# c150_rev_b.net
KiCad netlist of a schematic drawn in EAGLE
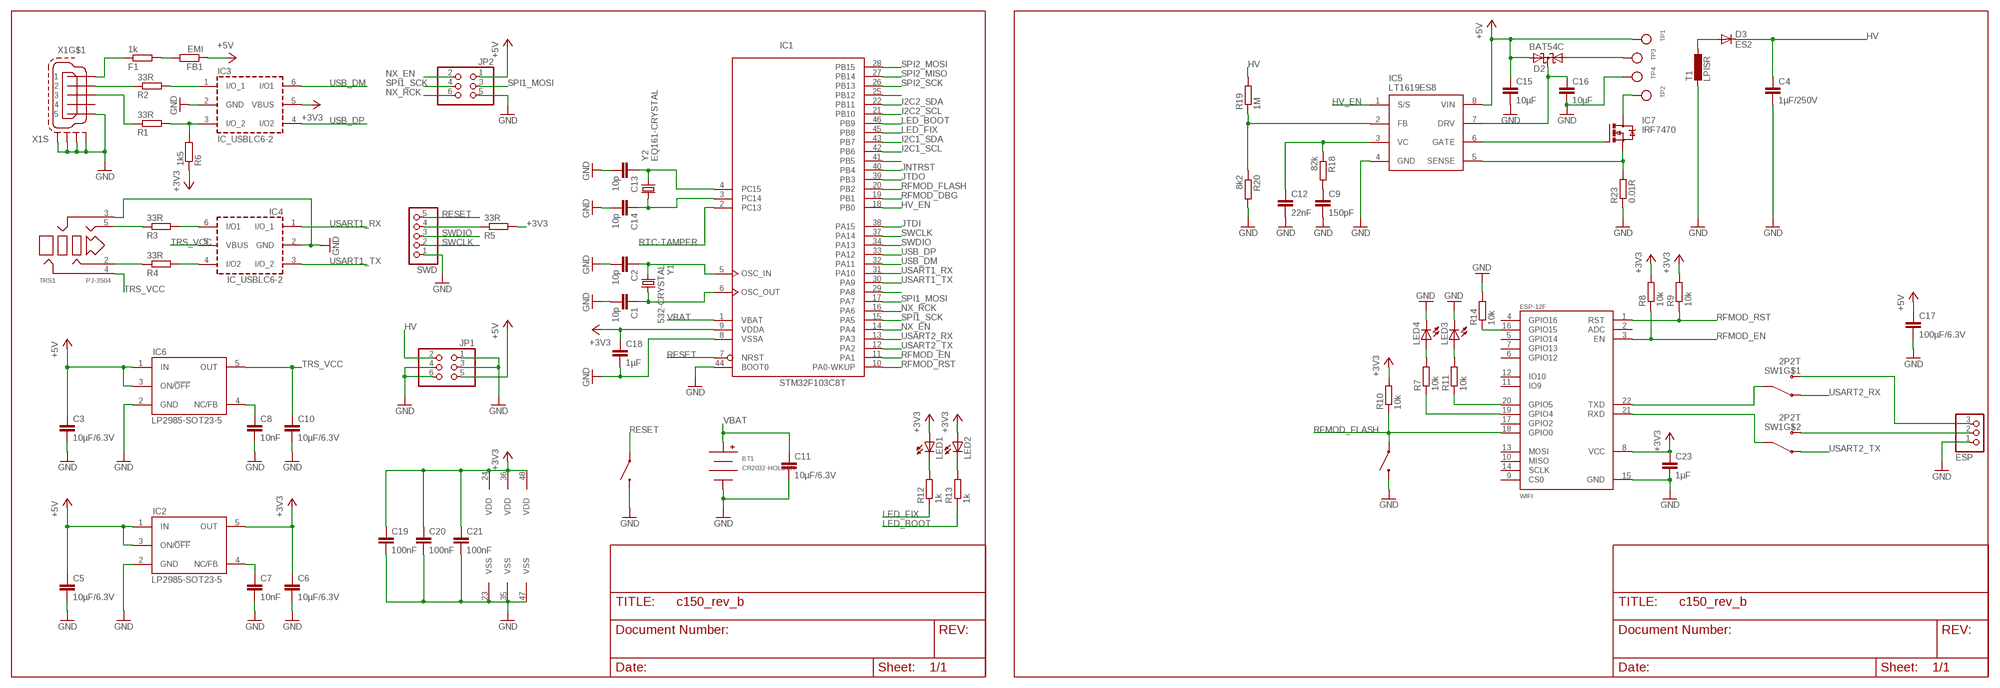
[diagram p0: schematic, sheet 1]

(export (version "E")
  (design (tool "Eeschema 10.0.6"))
  (components
    (comp (ref "BT1")
      (value "CR2032-HOLDER")
      (footprint "eagle-import:CH28-2032LF")
      (libsource (lib "eagle-import") (part "CR2032-HOLDER"))
    )
    (comp (ref "C1")
      (value "10p")
      (footprint "eagle-import:C0603")
      (libsource (lib "eagle-import") (part "C-EUC0603"))
    )
    (comp (ref "C2")
      (value "10p")
      (footprint "eagle-import:C0603")
      (libsource (lib "eagle-import") (part "C-EUC0603"))
    )
    (comp (ref "C3")
      (value "10µF/6.3V")
      (footprint "eagle-import:C0603")
      (libsource (lib "eagle-import") (part "C-EUC0603"))
    )
    (comp (ref "C4")
      (value "1µF/250V")
      (footprint "eagle-import:C2220K")
      (libsource (lib "eagle-import") (part "C-EUC2220K"))
    )
    (comp (ref "C5")
      (value "10µF/6.3V")
      (footprint "eagle-import:C0603")
      (libsource (lib "eagle-import") (part "C-EUC0603"))
    )
    (comp (ref "C6")
      (value "10µF/6.3V")
      (footprint "eagle-import:C0603")
      (libsource (lib "eagle-import") (part "C-EUC0603"))
    )
    (comp (ref "C7")
      (value "10nF")
      (footprint "eagle-import:C0603")
      (libsource (lib "eagle-import") (part "C-EUC0603"))
    )
    (comp (ref "C8")
      (value "10nF")
      (footprint "eagle-import:C0603")
      (libsource (lib "eagle-import") (part "C-EUC0603"))
    )
    (comp (ref "C9")
      (value "150pF")
      (footprint "eagle-import:C0603")
      (libsource (lib "eagle-import") (part "C-EUC0603"))
    )
    (comp (ref "C10")
      (value "10µF/6.3V")
      (footprint "eagle-import:C0603")
      (libsource (lib "eagle-import") (part "C-EUC0603"))
    )
    (comp (ref "C11")
      (value "10µF/6.3V")
      (footprint "eagle-import:C0603")
      (libsource (lib "eagle-import") (part "C-EUC0603"))
    )
    (comp (ref "C12")
      (value "22nF")
      (footprint "eagle-import:C0603")
      (libsource (lib "eagle-import") (part "C-EUC0603"))
    )
    (comp (ref "C13")
      (value "10p")
      (footprint "eagle-import:C0603")
      (libsource (lib "eagle-import") (part "C-EUC0603"))
    )
    (comp (ref "C14")
      (value "10p")
      (footprint "eagle-import:C0603")
      (libsource (lib "eagle-import") (part "C-EUC0603"))
    )
    (comp (ref "C15")
      (value "10µF")
      (footprint "eagle-import:C0603")
      (libsource (lib "eagle-import") (part "C-EUC0603"))
    )
    (comp (ref "C16")
      (value "10µF")
      (footprint "eagle-import:C0603")
      (libsource (lib "eagle-import") (part "C-EUC0603"))
    )
    (comp (ref "C17")
      (value "100µF/6.3V")
      (footprint "eagle-import:C1210")
      (libsource (lib "eagle-import") (part "C-EUC1210"))
    )
    (comp (ref "C18")
      (value "1µF")
      (footprint "eagle-import:C0603")
      (libsource (lib "eagle-import") (part "C-EUC0603"))
    )
    (comp (ref "C19")
      (value "100nF")
      (footprint "eagle-import:C0603")
      (libsource (lib "eagle-import") (part "C-EUC0603"))
    )
    (comp (ref "C20")
      (value "100nF")
      (footprint "eagle-import:C0603")
      (libsource (lib "eagle-import") (part "C-EUC0603"))
    )
    (comp (ref "C21")
      (value "100nF")
      (footprint "eagle-import:C0603")
      (libsource (lib "eagle-import") (part "C-EUC0603"))
    )
    (comp (ref "C23")
      (value "1µF")
      (footprint "eagle-import:C0603")
      (libsource (lib "eagle-import") (part "C-EUC0603"))
    )
    (comp (ref "D2")
      (value "BAT54C")
      (footprint "eagle-import:SOT23")
      (libsource (lib "eagle-import") (part "BAT54C"))
    )
    (comp (ref "D3")
      (value "ES2")
      (footprint "eagle-import:DO-214AA")
      (libsource (lib "eagle-import") (part "ES2"))
    )
    (comp (ref "ESP")
      (value "HEADER-1X3ROUND")
      (footprint "eagle-import:1X03_ROUND")
      (libsource (lib "eagle-import") (part "HEADER-1X3ROUND"))
    )
    (comp (ref "F1")
      (value "1k")
      (footprint "eagle-import:R0603")
      (libsource (lib "eagle-import") (part "R-EU_R0603"))
    )
    (comp (ref "FB1")
      (value "EMI")
      (footprint "eagle-import:R0603")
      (libsource (lib "eagle-import") (part "R-EU_R0603"))
    )
    (comp (ref "FLASH")
      (value "TACT-SWITCH-40-40")
      (footprint "eagle-import:40-40")
      (libsource (lib "eagle-import") (part "TACT-SWITCH-40-40"))
    )
    (comp (ref "IC1")
      (value "STM32F103C8T")
      (footprint "eagle-import:LQFP48")
      (libsource (lib "eagle-import") (part "STM32F103CT8"))
    )
    (comp (ref "IC2")
      (value "LP2985-SOT23-5")
      (footprint "eagle-import:SOT23-5")
      (libsource (lib "eagle-import") (part "LP2985-SOT23-5"))
    )
    (comp (ref "IC3")
      (value "IC_USBLC6-2")
      (footprint "eagle-import:SOT-23-6L")
      (libsource (lib "eagle-import") (part "IC_USBLC6-2"))
    )
    (comp (ref "IC4")
      (value "IC_USBLC6-2")
      (footprint "eagle-import:SOT-23-6L")
      (libsource (lib "eagle-import") (part "IC_USBLC6-2"))
    )
    (comp (ref "IC5")
      (value "LT1619ES8")
      (footprint "eagle-import:SO8")
      (libsource (lib "eagle-import") (part "LT1619ES8"))
    )
    (comp (ref "IC6")
      (value "LP2985-SOT23-5")
      (footprint "eagle-import:SOT23-5")
      (libsource (lib "eagle-import") (part "LP2985-SOT23-5"))
    )
    (comp (ref "IC7")
      (value "IRF7470")
      (footprint "eagle-import:SO8")
      (libsource (lib "eagle-import") (part "IRF7470"))
    )
    (comp (ref "ISP")
      (value "TACT-SWITCH-40-40")
      (footprint "eagle-import:40-40")
      (libsource (lib "eagle-import") (part "TACT-SWITCH-40-40"))
    )
    (comp (ref "JP1")
      (value "PINHD-2X3_2.54-SMD")
      (footprint "eagle-import:2X03SMD")
      (libsource (lib "eagle-import") (part "PINHD-2X3_2.54-SMD"))
    )
    (comp (ref "JP2")
      (value "PINHD-2X3_2.54-SMD")
      (footprint "eagle-import:2X03SMD")
      (libsource (lib "eagle-import") (part "PINHD-2X3_2.54-SMD"))
    )
    (comp (ref "LED1")
      (value "LEDCHIP-LED0603")
      (footprint "eagle-import:CHIP-LED0603")
      (libsource (lib "eagle-import") (part "LEDCHIP-LED0603"))
    )
    (comp (ref "LED2")
      (value "LEDCHIP-LED0603")
      (footprint "eagle-import:CHIP-LED0603")
      (libsource (lib "eagle-import") (part "LEDCHIP-LED0603"))
    )
    (comp (ref "LED3")
      (value "LEDCHIP-LED0603")
      (footprint "eagle-import:CHIP-LED0603")
      (libsource (lib "eagle-import") (part "LEDCHIP-LED0603"))
    )
    (comp (ref "LED4")
      (value "LEDCHIP-LED0603")
      (footprint "eagle-import:CHIP-LED0603")
      (libsource (lib "eagle-import") (part "LEDCHIP-LED0603"))
    )
    (comp (ref "R1")
      (value "33R")
      (footprint "eagle-import:R0603")
      (libsource (lib "eagle-import") (part "R-EU_R0603"))
    )
    (comp (ref "R2")
      (value "33R")
      (footprint "eagle-import:R0603")
      (libsource (lib "eagle-import") (part "R-EU_R0603"))
    )
    (comp (ref "R3")
      (value "33R")
      (footprint "eagle-import:R0603")
      (libsource (lib "eagle-import") (part "R-EU_R0603"))
    )
    (comp (ref "R4")
      (value "33R")
      (footprint "eagle-import:R0603")
      (libsource (lib "eagle-import") (part "R-EU_R0603"))
    )
    (comp (ref "R5")
      (value "33R")
      (footprint "eagle-import:R0603")
      (libsource (lib "eagle-import") (part "R-EU_R0603"))
    )
    (comp (ref "R6")
      (value "1k5")
      (footprint "eagle-import:R0603")
      (libsource (lib "eagle-import") (part "R-EU_R0603"))
    )
    (comp (ref "R7")
      (value "10k")
      (footprint "eagle-import:R0603")
      (libsource (lib "eagle-import") (part "R-EU_R0603"))
    )
    (comp (ref "R8")
      (value "10k")
      (footprint "eagle-import:R0603")
      (libsource (lib "eagle-import") (part "R-EU_R0603"))
    )
    (comp (ref "R9")
      (value "10k")
      (footprint "eagle-import:R0603")
      (libsource (lib "eagle-import") (part "R-EU_R0603"))
    )
    (comp (ref "R10")
      (value "10k")
      (footprint "eagle-import:R0603")
      (libsource (lib "eagle-import") (part "R-EU_R0603"))
    )
    (comp (ref "R11")
      (value "10k")
      (footprint "eagle-import:R0603")
      (libsource (lib "eagle-import") (part "R-EU_R0603"))
    )
    (comp (ref "R12")
      (value "1k")
      (footprint "eagle-import:R0603")
      (libsource (lib "eagle-import") (part "R-EU_R0603"))
    )
    (comp (ref "R13")
      (value "1k")
      (footprint "eagle-import:R0603")
      (libsource (lib "eagle-import") (part "R-EU_R0603"))
    )
    (comp (ref "R14")
      (value "10k")
      (footprint "eagle-import:R0603")
      (libsource (lib "eagle-import") (part "R-EU_R0603"))
    )
    (comp (ref "R18")
      (value "82k")
      (footprint "eagle-import:R0603")
      (libsource (lib "eagle-import") (part "R-EU_R0603"))
    )
    (comp (ref "R19")
      (value "1M")
      (footprint "eagle-import:M1206")
      (libsource (lib "eagle-import") (part "R-EU_M1206"))
    )
    (comp (ref "R20")
      (value "8k2")
      (footprint "eagle-import:R0603")
      (libsource (lib "eagle-import") (part "R-EU_R0603"))
    )
    (comp (ref "R23")
      (value "0.01R")
      (footprint "eagle-import:R1206")
      (libsource (lib "eagle-import") (part "R-EU_R1206"))
    )
    (comp (ref "SW1")
      (value "2P2T")
      (footprint "eagle-import:MSS22D18")
      (libsource (lib "eagle-import") (part "2P2T"))
    )
    (comp (ref "SWD")
      (value "HEADER-1X5ROUND")
      (footprint "eagle-import:1X05_ROUND")
      (libsource (lib "eagle-import") (part "HEADER-1X5ROUND"))
    )
    (comp (ref "T1")
      (value "LPISR")
      (footprint "eagle-import:PISR")
      (libsource (lib "eagle-import") (part "LPISR"))
    )
    (comp (ref "TP1")
      (value "TESTPOINTROUND2MM")
      (footprint "eagle-import:TESTPOINT_ROUND_2MM")
      (libsource (lib "eagle-import") (part "TESTPOINTROUND2MM"))
    )
    (comp (ref "TP2")
      (value "TESTPOINTROUND2MM")
      (footprint "eagle-import:TESTPOINT_ROUND_2MM")
      (libsource (lib "eagle-import") (part "TESTPOINTROUND2MM"))
    )
    (comp (ref "TP3")
      (value "TESTPOINTROUND2MM")
      (footprint "eagle-import:TESTPOINT_ROUND_2MM")
      (libsource (lib "eagle-import") (part "TESTPOINTROUND2MM"))
    )
    (comp (ref "TP4")
      (value "TESTPOINTROUND2MM")
      (footprint "eagle-import:TESTPOINT_ROUND_2MM")
      (libsource (lib "eagle-import") (part "TESTPOINTROUND2MM"))
    )
    (comp (ref "TRS1")
      (value "PJ-3504")
      (footprint "eagle-import:YD-PJ-3504")
      (libsource (lib "eagle-import") (part "PJ-3504"))
    )
    (comp (ref "WIFI")
      (value "ESP-12F")
      (footprint "eagle-import:ESP-12F")
      (libsource (lib "eagle-import") (part "ESP-12F"))
    )
    (comp (ref "X1")
      (value "MINI-USB-SCHIELD-32005-201")
      (footprint "eagle-import:32005-201")
      (libsource (lib "eagle-import") (part "MINI-USB-SCHIELD-32005-201"))
    )
    (comp (ref "Y1")
      (value "532-CRYSTAL")
      (footprint "eagle-import:2PIN50X32")
      (libsource (lib "eagle-import") (part "532-CRYSTAL"))
    )
    (comp (ref "Y2")
      (value "EQ161-CRYSTAL")
      (footprint "eagle-import:EQ161")
      (libsource (lib "eagle-import") (part "EQ161-CRYSTAL"))
    )
  )
  (nets
    (net (code "1") (name "+3V3") (class "Default")
      (node (ref "C18") (pin "1") (pinfunction "1_1") (pintype "passive"))
      (node (ref "C19") (pin "1") (pinfunction "1_1") (pintype "passive"))
      (node (ref "C20") (pin "1") (pinfunction "1_1") (pintype "passive"))
      (node (ref "C21") (pin "1") (pinfunction "1_1") (pintype "passive"))
      (node (ref "C23") (pin "1") (pinfunction "1_1") (pintype "passive"))
      (node (ref "C6") (pin "1") (pinfunction "1_1") (pintype "passive"))
      (node (ref "IC1") (pin "24") (pinfunction "VDD_24") (pintype "power_in"))
      (node (ref "IC1") (pin "36") (pinfunction "VDD_36") (pintype "power_in"))
      (node (ref "IC1") (pin "48") (pinfunction "VDD_48") (pintype "power_in"))
      (node (ref "IC1") (pin "9") (pinfunction "VDDA_9") (pintype "power_in"))
      (node (ref "IC2") (pin "5") (pinfunction "OUT_5") (pintype "bidirectional"))
      (node (ref "IC3") (pin "5") (pinfunction "VBUS_5") (pintype "bidirectional"))
      (node (ref "LED1") (pin "A") (pinfunction "A_A") (pintype "passive"))
      (node (ref "LED2") (pin "A") (pinfunction "A_A") (pintype "passive"))
      (node (ref "R10") (pin "2") (pinfunction "2_2") (pintype "passive"))
      (node (ref "R5") (pin "2") (pinfunction "2_2") (pintype "passive"))
      (node (ref "R6") (pin "1") (pinfunction "1_1") (pintype "passive"))
      (node (ref "R8") (pin "2") (pinfunction "2_2") (pintype "passive"))
      (node (ref "R9") (pin "2") (pinfunction "2_2") (pintype "passive"))
      (node (ref "WIFI") (pin "8") (pinfunction "VCC_8") (pintype "bidirectional"))
    )
    (net (code "2") (name "+5V") (class "Default")
      (node (ref "C15") (pin "1") (pinfunction "1_1") (pintype "passive"))
      (node (ref "C17") (pin "1") (pinfunction "1_1") (pintype "passive"))
      (node (ref "C3") (pin "1") (pinfunction "1_1") (pintype "passive"))
      (node (ref "C5") (pin "1") (pinfunction "1_1") (pintype "passive"))
      (node (ref "D2") (pin "2") (pinfunction "A2_2") (pintype "passive"))
      (node (ref "FB1") (pin "1") (pinfunction "1_1") (pintype "passive"))
      (node (ref "IC2") (pin "1") (pinfunction "IN_1") (pintype "bidirectional"))
      (node (ref "IC2") (pin "3") (pinfunction "ON/~{OFF}_3") (pintype "bidirectional"))
      (node (ref "IC5") (pin "8") (pinfunction "VIN_8") (pintype "bidirectional"))
      (node (ref "IC6") (pin "1") (pinfunction "IN_1") (pintype "bidirectional"))
      (node (ref "IC6") (pin "3") (pinfunction "ON/~{OFF}_3") (pintype "bidirectional"))
      (node (ref "JP1") (pin "5") (pinfunction "5_5") (pintype "passive"))
      (node (ref "JP2") (pin "1") (pinfunction "1_1") (pintype "passive"))
      (node (ref "TP1") (pin "P$1") (pinfunction "P$1_P$1") (pintype "bidirectional"))
    )
    (net (code "3") (name "/HV") (class "Default")
      (node (ref "C4") (pin "1") (pinfunction "1_1") (pintype "passive"))
      (node (ref "D3") (pin "C") (pinfunction "C_C") (pintype "passive"))
      (node (ref "JP1") (pin "2") (pinfunction "2_2") (pintype "passive"))
      (node (ref "R19") (pin "2") (pinfunction "2_2") (pintype "passive"))
    )
    (net (code "4") (name "/HV_EN") (class "Default")
      (node (ref "IC1") (pin "18") (pinfunction "PB0_18") (pintype "bidirectional"))
      (node (ref "IC5") (pin "1") (pinfunction "S/S_1") (pintype "bidirectional"))
    )
    (net (code "5") (name "/I2C1_SCL") (class "Default")
      (node (ref "IC1") (pin "42") (pinfunction "PB6_42") (pintype "bidirectional"))
    )
    (net (code "6") (name "/I2C1_SDA") (class "Default")
      (node (ref "IC1") (pin "43") (pinfunction "PB7_43") (pintype "bidirectional"))
    )
    (net (code "7") (name "/I2C2_SCL") (class "Default")
      (node (ref "IC1") (pin "21") (pinfunction "PB10_21") (pintype "bidirectional"))
    )
    (net (code "8") (name "/I2C2_SDA") (class "Default")
      (node (ref "IC1") (pin "22") (pinfunction "PB11_22") (pintype "bidirectional"))
    )
    (net (code "9") (name "/JNTRST") (class "Default")
      (node (ref "IC1") (pin "40") (pinfunction "PB4_40") (pintype "bidirectional"))
    )
    (net (code "10") (name "/JTDI") (class "Default")
      (node (ref "IC1") (pin "38") (pinfunction "PA15_38") (pintype "bidirectional"))
    )
    (net (code "11") (name "/JTDO") (class "Default")
      (node (ref "IC1") (pin "39") (pinfunction "PB3_39") (pintype "bidirectional"))
    )
    (net (code "12") (name "/LED_BOOT") (class "Default")
      (node (ref "IC1") (pin "46") (pinfunction "PB9_46") (pintype "bidirectional"))
      (node (ref "R13") (pin "1") (pinfunction "1_1") (pintype "passive"))
    )
    (net (code "13") (name "/LED_FIX") (class "Default")
      (node (ref "IC1") (pin "45") (pinfunction "PB8_45") (pintype "bidirectional"))
      (node (ref "R12") (pin "1") (pinfunction "1_1") (pintype "passive"))
    )
    (net (code "14") (name "/NX_EN") (class "Default")
      (node (ref "IC1") (pin "14") (pinfunction "PA4_14") (pintype "bidirectional"))
      (node (ref "JP2") (pin "2") (pinfunction "2_2") (pintype "passive"))
    )
    (net (code "15") (name "/NX_RCK") (class "Default")
      (node (ref "IC1") (pin "16") (pinfunction "PA6_16") (pintype "bidirectional"))
      (node (ref "JP2") (pin "6") (pinfunction "6_6") (pintype "passive"))
    )
    (net (code "16") (name "/RESET") (class "Default")
      (node (ref "IC1") (pin "7") (pinfunction "NRST_7") (pintype "bidirectional"))
      (node (ref "ISP") (pin "3") (pinfunction "P$2_3") (pintype "bidirectional"))
      (node (ref "ISP") (pin "4") (pinfunction "P$2_4") (pintype "bidirectional"))
      (node (ref "SWD") (pin "5") (pinfunction "5_5") (pintype "passive"))
    )
    (net (code "17") (name "/RFMOD_DBG") (class "Default")
      (node (ref "IC1") (pin "19") (pinfunction "PB1_19") (pintype "bidirectional"))
    )
    (net (code "18") (name "/RFMOD_EN") (class "Default")
      (node (ref "IC1") (pin "11") (pinfunction "PA1_11") (pintype "bidirectional"))
      (node (ref "R8") (pin "1") (pinfunction "1_1") (pintype "passive"))
      (node (ref "WIFI") (pin "3") (pinfunction "EN_3") (pintype "bidirectional"))
    )
    (net (code "19") (name "/RFMOD_FLASH") (class "Default")
      (node (ref "FLASH") (pin "3") (pinfunction "P$2_3") (pintype "bidirectional"))
      (node (ref "FLASH") (pin "4") (pinfunction "P$2_4") (pintype "bidirectional"))
      (node (ref "IC1") (pin "20") (pinfunction "PB2_20") (pintype "bidirectional"))
      (node (ref "R10") (pin "1") (pinfunction "1_1") (pintype "passive"))
      (node (ref "WIFI") (pin "18") (pinfunction "GPIO0_18") (pintype "bidirectional"))
    )
    (net (code "20") (name "/RFMOD_RST") (class "Default")
      (node (ref "IC1") (pin "10") (pinfunction "PA0-WKUP_10") (pintype "bidirectional"))
      (node (ref "R9") (pin "1") (pinfunction "1_1") (pintype "passive"))
      (node (ref "WIFI") (pin "1") (pinfunction "RST_1") (pintype "bidirectional"))
    )
    (net (code "21") (name "/RTC-TAMPER") (class "Default")
      (node (ref "IC1") (pin "2") (pinfunction "PC13_2") (pintype "bidirectional"))
    )
    (net (code "22") (name "/SPI1_MOSI") (class "Default")
      (node (ref "IC1") (pin "17") (pinfunction "PA7_17") (pintype "bidirectional"))
      (node (ref "JP2") (pin "3") (pinfunction "3_3") (pintype "passive"))
    )
    (net (code "23") (name "/SPI1_SCK") (class "Default")
      (node (ref "IC1") (pin "15") (pinfunction "PA5_15") (pintype "bidirectional"))
      (node (ref "JP2") (pin "4") (pinfunction "4_4") (pintype "passive"))
    )
    (net (code "24") (name "/SPI2_MISO") (class "Default")
      (node (ref "IC1") (pin "27") (pinfunction "PB14_27") (pintype "bidirectional"))
    )
    (net (code "25") (name "/SPI2_MOSI") (class "Default")
      (node (ref "IC1") (pin "28") (pinfunction "PB15_28") (pintype "bidirectional"))
    )
    (net (code "26") (name "/SPI2_SCK") (class "Default")
      (node (ref "IC1") (pin "26") (pinfunction "PB13_26") (pintype "bidirectional"))
    )
    (net (code "27") (name "/SWCLK") (class "Default")
      (node (ref "IC1") (pin "37") (pinfunction "PA14_37") (pintype "bidirectional"))
      (node (ref "SWD") (pin "2") (pinfunction "2_2") (pintype "passive"))
    )
    (net (code "28") (name "/SWDIO") (class "Default")
      (node (ref "IC1") (pin "34") (pinfunction "PA13_34") (pintype "bidirectional"))
      (node (ref "SWD") (pin "3") (pinfunction "3_3") (pintype "passive"))
    )
    (net (code "29") (name "/TRS_VCC") (class "Default")
      (node (ref "C10") (pin "1") (pinfunction "1_1") (pintype "passive"))
      (node (ref "IC4") (pin "5") (pinfunction "VBUS_5") (pintype "bidirectional"))
      (node (ref "IC6") (pin "5") (pinfunction "OUT_5") (pintype "bidirectional"))
      (node (ref "TRS1") (pin "4") (pinfunction "4_4") (pintype "bidirectional"))
    )
    (net (code "30") (name "/USART1_RX") (class "Default")
      (node (ref "IC1") (pin "31") (pinfunction "PA10_31") (pintype "bidirectional"))
      (node (ref "IC4") (pin "1") (pinfunction "I/O_1_1") (pintype "bidirectional"))
    )
    (net (code "31") (name "/USART1_TX") (class "Default")
      (node (ref "IC1") (pin "30") (pinfunction "PA9_30") (pintype "bidirectional"))
      (node (ref "IC4") (pin "3") (pinfunction "I/O_2_3") (pintype "bidirectional"))
    )
    (net (code "32") (name "/USART2_RX") (class "Default")
      (node (ref "IC1") (pin "13") (pinfunction "PA3_13") (pintype "bidirectional"))
      (node (ref "SW1") (pin "A1") (pinfunction "A_A1") (pintype "bidirectional"))
    )
    (net (code "33") (name "/USART2_TX") (class "Default")
      (node (ref "IC1") (pin "12") (pinfunction "PA2_12") (pintype "bidirectional"))
      (node (ref "SW1") (pin "A2") (pinfunction "A_A2") (pintype "bidirectional"))
    )
    (net (code "34") (name "/USB_DM") (class "Default")
      (node (ref "IC1") (pin "32") (pinfunction "PA11_32") (pintype "bidirectional"))
      (node (ref "IC3") (pin "6") (pinfunction "I/O1_6") (pintype "bidirectional"))
    )
    (net (code "35") (name "/USB_DP") (class "Default")
      (node (ref "IC1") (pin "33") (pinfunction "PA12_33") (pintype "bidirectional"))
      (node (ref "IC3") (pin "4") (pinfunction "I/O2_4") (pintype "bidirectional"))
    )
    (net (code "36") (name "/VBAT") (class "Default")
      (node (ref "BT1") (pin "POS") (pinfunction "POS_POS") (pintype "bidirectional"))
      (node (ref "C11") (pin "1") (pinfunction "1_1") (pintype "passive"))
      (node (ref "IC1") (pin "1") (pinfunction "VBAT_1") (pintype "power_in"))
    )
    (net (code "37") (name "GND") (class "Default")
      (node (ref "BT1") (pin "NEG") (pinfunction "NEG_NEG") (pintype "bidirectional"))
      (node (ref "C1") (pin "2") (pinfunction "2_2") (pintype "passive"))
      (node (ref "C10") (pin "2") (pinfunction "2_2") (pintype "passive"))
      (node (ref "C11") (pin "2") (pinfunction "2_2") (pintype "passive"))
      (node (ref "C12") (pin "2") (pinfunction "2_2") (pintype "passive"))
      (node (ref "C13") (pin "2") (pinfunction "2_2") (pintype "passive"))
      (node (ref "C14") (pin "2") (pinfunction "2_2") (pintype "passive"))
      (node (ref "C15") (pin "2") (pinfunction "2_2") (pintype "passive"))
      (node (ref "C16") (pin "2") (pinfunction "2_2") (pintype "passive"))
      (node (ref "C17") (pin "2") (pinfunction "2_2") (pintype "passive"))
      (node (ref "C18") (pin "2") (pinfunction "2_2") (pintype "passive"))
      (node (ref "C19") (pin "2") (pinfunction "2_2") (pintype "passive"))
      (node (ref "C2") (pin "2") (pinfunction "2_2") (pintype "passive"))
      (node (ref "C20") (pin "2") (pinfunction "2_2") (pintype "passive"))
      (node (ref "C21") (pin "2") (pinfunction "2_2") (pintype "passive"))
      (node (ref "C23") (pin "2") (pinfunction "2_2") (pintype "passive"))
      (node (ref "C3") (pin "2") (pinfunction "2_2") (pintype "passive"))
      (node (ref "C4") (pin "2") (pinfunction "2_2") (pintype "passive"))
      (node (ref "C5") (pin "2") (pinfunction "2_2") (pintype "passive"))
      (node (ref "C6") (pin "2") (pinfunction "2_2") (pintype "passive"))
      (node (ref "C7") (pin "2") (pinfunction "2_2") (pintype "passive"))
      (node (ref "C8") (pin "2") (pinfunction "2_2") (pintype "passive"))
      (node (ref "C9") (pin "2") (pinfunction "2_2") (pintype "passive"))
      (node (ref "ESP") (pin "1") (pinfunction "1_1") (pintype "passive"))
      (node (ref "FLASH") (pin "1") (pinfunction "P$1_1") (pintype "bidirectional"))
      (node (ref "FLASH") (pin "2") (pinfunction "P$1_2") (pintype "bidirectional"))
      (node (ref "IC1") (pin "23") (pinfunction "VSS_23") (pintype "power_in"))
      (node (ref "IC1") (pin "35") (pinfunction "VSS_35") (pintype "power_in"))
      (node (ref "IC1") (pin "44") (pinfunction "BOOT0_44") (pintype "input"))
      (node (ref "IC1") (pin "47") (pinfunction "VSS_47") (pintype "power_in"))
      (node (ref "IC1") (pin "8") (pinfunction "VSSA_8") (pintype "power_in"))
      (node (ref "IC2") (pin "2") (pinfunction "GND_2") (pintype "bidirectional"))
      (node (ref "IC3") (pin "2") (pinfunction "GND_2") (pintype "bidirectional"))
      (node (ref "IC4") (pin "2") (pinfunction "GND_2") (pintype "bidirectional"))
      (node (ref "IC5") (pin "4") (pinfunction "GND_4") (pintype "bidirectional"))
      (node (ref "IC6") (pin "2") (pinfunction "GND_2") (pintype "bidirectional"))
      (node (ref "ISP") (pin "1") (pinfunction "P$1_1") (pintype "bidirectional"))
      (node (ref "ISP") (pin "2") (pinfunction "P$1_2") (pintype "bidirectional"))
      (node (ref "JP1") (pin "1") (pinfunction "1_1") (pintype "passive"))
      (node (ref "JP1") (pin "3") (pinfunction "3_3") (pintype "passive"))
      (node (ref "JP1") (pin "4") (pinfunction "4_4") (pintype "passive"))
      (node (ref "JP1") (pin "6") (pinfunction "6_6") (pintype "passive"))
      (node (ref "JP2") (pin "5") (pinfunction "5_5") (pintype "passive"))
      (node (ref "LED3") (pin "C") (pinfunction "C_C") (pintype "passive"))
      (node (ref "LED4") (pin "C") (pinfunction "C_C") (pintype "passive"))
      (node (ref "R14") (pin "2") (pinfunction "2_2") (pintype "passive"))
      (node (ref "R20") (pin "2") (pinfunction "2_2") (pintype "passive"))
      (node (ref "R23") (pin "1") (pinfunction "1_1") (pintype "passive"))
      (node (ref "SWD") (pin "1") (pinfunction "1_1") (pintype "passive"))
      (node (ref "T1") (pin "P$2") (pinfunction "2_P$2") (pintype "passive"))
      (node (ref "TP4") (pin "P$1") (pinfunction "P$1_P$1") (pintype "bidirectional"))
      (node (ref "TRS1") (pin "3") (pinfunction "3_3") (pintype "bidirectional"))
      (node (ref "WIFI") (pin "15") (pinfunction "GND_15") (pintype "bidirectional"))
      (node (ref "X1") (pin "5") (pinfunction "5_5") (pintype "passive"))
      (node (ref "X1") (pin "M1") (pinfunction "S1_M1") (pintype "passive"))
      (node (ref "X1") (pin "M2") (pinfunction "S2_M2") (pintype "passive"))
      (node (ref "X1") (pin "M3") (pinfunction "S3_M3") (pintype "passive"))
      (node (ref "X1") (pin "M4") (pinfunction "S4_M4") (pintype "passive"))
    )
    (net (code "38") (name "Net-(C9-Pad1)") (class "Default")
      (node (ref "C9") (pin "1") (pinfunction "1_1") (pintype "passive"))
      (node (ref "R18") (pin "2") (pinfunction "2_2") (pintype "passive"))
    )
    (net (code "39") (name "Net-(D2-A1)") (class "Default")
      (node (ref "D2") (pin "1") (pinfunction "A1_1") (pintype "passive"))
      (node (ref "TP3") (pin "P$1") (pinfunction "P$1_P$1") (pintype "bidirectional"))
    )
    (net (code "40") (name "Net-(D2-CC)") (class "Default")
      (node (ref "C16") (pin "1") (pinfunction "1_1") (pintype "passive"))
      (node (ref "D2") (pin "3") (pinfunction "CC_3") (pintype "passive"))
      (node (ref "IC5") (pin "7") (pinfunction "DRV_7") (pintype "bidirectional"))
    )
    (net (code "41") (name "Net-(F1-Pad1)") (class "Default")
      (node (ref "F1") (pin "1") (pinfunction "1_1") (pintype "passive"))
      (node (ref "X1") (pin "1") (pinfunction "1_1") (pintype "passive"))
    )
    (net (code "42") (name "Net-(F1-Pad2)") (class "Default")
      (node (ref "F1") (pin "2") (pinfunction "2_2") (pintype "passive"))
      (node (ref "FB1") (pin "2") (pinfunction "2_2") (pintype "passive"))
    )
    (net (code "43") (name "Net-(IC1A-OSC_IN)") (class "Default")
      (node (ref "C2") (pin "1") (pinfunction "1_1") (pintype "passive"))
      (node (ref "IC1") (pin "5") (pinfunction "OSC_IN_5") (pintype "bidirectional"))
      (node (ref "Y1") (pin "P$2") (pinfunction "2_P$2") (pintype "passive"))
    )
    (net (code "44") (name "Net-(IC1A-OSC_OUT)") (class "Default")
      (node (ref "C1") (pin "1") (pinfunction "1_1") (pintype "passive"))
      (node (ref "IC1") (pin "6") (pinfunction "OSC_OUT_6") (pintype "bidirectional"))
      (node (ref "Y1") (pin "P$1") (pinfunction "1_P$1") (pintype "passive"))
    )
    (net (code "45") (name "Net-(IC1A-PC14)") (class "Default")
      (node (ref "C14") (pin "1") (pinfunction "1_1") (pintype "passive"))
      (node (ref "IC1") (pin "3") (pinfunction "PC14_3") (pintype "bidirectional"))
      (node (ref "Y2") (pin "P$2") (pinfunction "2_P$2") (pintype "passive"))
    )
    (net (code "46") (name "Net-(IC1A-PC15)") (class "Default")
      (node (ref "C13") (pin "1") (pinfunction "1_1") (pintype "passive"))
      (node (ref "IC1") (pin "4") (pinfunction "PC15_4") (pintype "bidirectional"))
      (node (ref "Y2") (pin "P$1") (pinfunction "1_P$1") (pintype "passive"))
    )
    (net (code "47") (name "Net-(IC2-NC{slash}FB)") (class "Default")
      (node (ref "C7") (pin "1") (pinfunction "1_1") (pintype "passive"))
      (node (ref "IC2") (pin "4") (pinfunction "NC/FB_4") (pintype "bidirectional"))
    )
    (net (code "48") (name "Net-(IC3-I{slash}O_1)") (class "Default")
      (node (ref "IC3") (pin "1") (pinfunction "I/O_1_1") (pintype "bidirectional"))
      (node (ref "R2") (pin "2") (pinfunction "2_2") (pintype "passive"))
    )
    (net (code "49") (name "Net-(IC3-I{slash}O_2)") (class "Default")
      (node (ref "IC3") (pin "3") (pinfunction "I/O_2_3") (pintype "bidirectional"))
      (node (ref "R1") (pin "2") (pinfunction "2_2") (pintype "passive"))
      (node (ref "R6") (pin "2") (pinfunction "2_2") (pintype "passive"))
    )
    (net (code "50") (name "Net-(IC4-I{slash}O1)") (class "Default")
      (node (ref "IC4") (pin "6") (pinfunction "I/O1_6") (pintype "bidirectional"))
      (node (ref "R3") (pin "2") (pinfunction "2_2") (pintype "passive"))
    )
    (net (code "51") (name "Net-(IC4-I{slash}O2)") (class "Default")
      (node (ref "IC4") (pin "4") (pinfunction "I/O2_4") (pintype "bidirectional"))
      (node (ref "R4") (pin "2") (pinfunction "2_2") (pintype "passive"))
    )
    (net (code "52") (name "Net-(IC5-FB)") (class "Default")
      (node (ref "IC5") (pin "2") (pinfunction "FB_2") (pintype "bidirectional"))
      (node (ref "R19") (pin "1") (pinfunction "1_1") (pintype "passive"))
      (node (ref "R20") (pin "1") (pinfunction "1_1") (pintype "passive"))
    )
    (net (code "53") (name "Net-(IC5-GATE)") (class "Default")
      (node (ref "IC5") (pin "6") (pinfunction "GATE_6") (pintype "bidirectional"))
      (node (ref "IC7") (pin "4") (pinfunction "G_4") (pintype "passive"))
    )
    (net (code "54") (name "Net-(IC5-SENSE)") (class "Default")
      (node (ref "IC5") (pin "5") (pinfunction "SENSE_5") (pintype "bidirectional"))
      (node (ref "IC7") (pin "1") (pinfunction "S_1") (pintype "passive"))
      (node (ref "IC7") (pin "2") (pinfunction "S_2") (pintype "passive"))
      (node (ref "IC7") (pin "3") (pinfunction "S_3") (pintype "passive"))
      (node (ref "R23") (pin "2") (pinfunction "2_2") (pintype "passive"))
    )
    (net (code "55") (name "Net-(IC5-VC)") (class "Default")
      (node (ref "C12") (pin "1") (pinfunction "1_1") (pintype "passive"))
      (node (ref "IC5") (pin "3") (pinfunction "VC_3") (pintype "bidirectional"))
      (node (ref "R18") (pin "1") (pinfunction "1_1") (pintype "passive"))
    )
    (net (code "56") (name "Net-(IC6-NC{slash}FB)") (class "Default")
      (node (ref "C8") (pin "1") (pinfunction "1_1") (pintype "passive"))
      (node (ref "IC6") (pin "4") (pinfunction "NC/FB_4") (pintype "bidirectional"))
    )
    (net (code "57") (name "Net-(IC7-D-Pad5)") (class "Default")
      (node (ref "IC7") (pin "5") (pinfunction "D_5") (pintype "passive"))
      (node (ref "IC7") (pin "6") (pinfunction "D_6") (pintype "passive"))
      (node (ref "IC7") (pin "7") (pinfunction "D_7") (pintype "passive"))
      (node (ref "IC7") (pin "8") (pinfunction "D_8") (pintype "passive"))
      (node (ref "TP2") (pin "P$1") (pinfunction "P$1_P$1") (pintype "bidirectional"))
    )
    (net (code "58") (name "Net-(LED1-PadC)") (class "Default")
      (node (ref "LED1") (pin "C") (pinfunction "C_C") (pintype "passive"))
      (node (ref "R12") (pin "2") (pinfunction "2_2") (pintype "passive"))
    )
    (net (code "59") (name "Net-(LED2-PadC)") (class "Default")
      (node (ref "LED2") (pin "C") (pinfunction "C_C") (pintype "passive"))
      (node (ref "R13") (pin "2") (pinfunction "2_2") (pintype "passive"))
    )
    (net (code "60") (name "Net-(LED3-PadA)") (class "Default")
      (node (ref "LED3") (pin "A") (pinfunction "A_A") (pintype "passive"))
      (node (ref "R11") (pin "2") (pinfunction "2_2") (pintype "passive"))
    )
    (net (code "61") (name "Net-(LED4-PadA)") (class "Default")
      (node (ref "LED4") (pin "A") (pinfunction "A_A") (pintype "passive"))
      (node (ref "R7") (pin "2") (pinfunction "2_2") (pintype "passive"))
    )
    (net (code "62") (name "Net-(R1-Pad1)") (class "Default")
      (node (ref "R1") (pin "1") (pinfunction "1_1") (pintype "passive"))
      (node (ref "X1") (pin "3") (pinfunction "3_3") (pintype "passive"))
    )
    (net (code "63") (name "Net-(R2-Pad1)") (class "Default")
      (node (ref "R2") (pin "1") (pinfunction "1_1") (pintype "passive"))
      (node (ref "X1") (pin "2") (pinfunction "2_2") (pintype "passive"))
    )
    (net (code "64") (name "Net-(R3-Pad1)") (class "Default")
      (node (ref "R3") (pin "1") (pinfunction "1_1") (pintype "passive"))
      (node (ref "TRS1") (pin "5") (pinfunction "5_5") (pintype "bidirectional"))
    )
    (net (code "65") (name "Net-(R4-Pad1)") (class "Default")
      (node (ref "R4") (pin "1") (pinfunction "1_1") (pintype "passive"))
      (node (ref "TRS1") (pin "2") (pinfunction "2_2") (pintype "bidirectional"))
    )
    (net (code "66") (name "Net-(R5-Pad1)") (class "Default")
      (node (ref "R5") (pin "1") (pinfunction "1_1") (pintype "passive"))
      (node (ref "SWD") (pin "4") (pinfunction "4_4") (pintype "passive"))
    )
    (net (code "67") (name "Net-(SW1A-B)") (class "Default")
      (node (ref "ESP") (pin "3") (pinfunction "3_3") (pintype "passive"))
      (node (ref "SW1") (pin "B1") (pinfunction "B_B1") (pintype "bidirectional"))
    )
    (net (code "68") (name "Net-(SW1A-C)") (class "Default")
      (node (ref "SW1") (pin "C1") (pinfunction "C_C1") (pintype "bidirectional"))
      (node (ref "WIFI") (pin "22") (pinfunction "TXD_22") (pintype "bidirectional"))
    )
    (net (code "69") (name "Net-(SW1B-B)") (class "Default")
      (node (ref "ESP") (pin "2") (pinfunction "2_2") (pintype "passive"))
      (node (ref "SW1") (pin "B2") (pinfunction "B_B2") (pintype "bidirectional"))
    )
    (net (code "70") (name "Net-(SW1B-C)") (class "Default")
      (node (ref "SW1") (pin "C2") (pinfunction "C_C2") (pintype "bidirectional"))
      (node (ref "WIFI") (pin "21") (pinfunction "RXD_21") (pintype "bidirectional"))
    )
    (net (code "71") (name "Net-(T1-1)") (class "Default")
      (node (ref "D3") (pin "A") (pinfunction "A_A") (pintype "passive"))
      (node (ref "T1") (pin "P$1") (pinfunction "1_P$1") (pintype "passive"))
    )
    (net (code "72") (name "Net-(WIFI-GPIO4)") (class "Default")
      (node (ref "R7") (pin "1") (pinfunction "1_1") (pintype "passive"))
      (node (ref "WIFI") (pin "19") (pinfunction "GPIO4_19") (pintype "bidirectional"))
    )
    (net (code "73") (name "Net-(WIFI-GPIO5)") (class "Default")
      (node (ref "R11") (pin "1") (pinfunction "1_1") (pintype "passive"))
      (node (ref "WIFI") (pin "20") (pinfunction "GPIO5_20") (pintype "bidirectional"))
    )
    (net (code "74") (name "Net-(WIFI-GPIO15)") (class "Default")
      (node (ref "R14") (pin "1") (pinfunction "1_1") (pintype "passive"))
      (node (ref "WIFI") (pin "16") (pinfunction "GPIO15_16") (pintype "bidirectional"))
    )
    (net (code "75") (name "unconnected-(IC1A-PA8-Pad29)") (class "Default")
      (node (ref "IC1") (pin "29") (pinfunction "PA8_29") (pintype "bidirectional"))
    )
    (net (code "76") (name "unconnected-(IC1A-PB5-Pad41)") (class "Default")
      (node (ref "IC1") (pin "41") (pinfunction "PB5_41") (pintype "bidirectional"))
    )
    (net (code "77") (name "unconnected-(IC1A-PB12-Pad25)") (class "Default")
      (node (ref "IC1") (pin "25") (pinfunction "PB12_25") (pintype "bidirectional"))
    )
    (net (code "78") (name "unconnected-(WIFI-ADC-Pad2)") (class "Default")
      (node (ref "WIFI") (pin "2") (pinfunction "ADC_2") (pintype "bidirectional"))
    )
    (net (code "79") (name "unconnected-(WIFI-CS0-Pad9)") (class "Default")
      (node (ref "WIFI") (pin "9") (pinfunction "CS0_9") (pintype "bidirectional"))
    )
    (net (code "80") (name "unconnected-(WIFI-GPIO2-Pad17)") (class "Default")
      (node (ref "WIFI") (pin "17") (pinfunction "GPIO2_17") (pintype "bidirectional"))
    )
    (net (code "81") (name "unconnected-(WIFI-GPIO12-Pad6)") (class "Default")
      (node (ref "WIFI") (pin "6") (pinfunction "GPIO12_6") (pintype "bidirectional"))
    )
    (net (code "82") (name "unconnected-(WIFI-GPIO13-Pad7)") (class "Default")
      (node (ref "WIFI") (pin "7") (pinfunction "GPIO13_7") (pintype "bidirectional"))
    )
    (net (code "83") (name "unconnected-(WIFI-GPIO14-Pad5)") (class "Default")
      (node (ref "WIFI") (pin "5") (pinfunction "GPIO14_5") (pintype "bidirectional"))
    )
    (net (code "84") (name "unconnected-(WIFI-GPIO16-Pad4)") (class "Default")
      (node (ref "WIFI") (pin "4") (pinfunction "GPIO16_4") (pintype "bidirectional"))
    )
    (net (code "85") (name "unconnected-(WIFI-IO9-Pad11)") (class "Default")
      (node (ref "WIFI") (pin "11") (pinfunction "IO9_11") (pintype "bidirectional"))
    )
    (net (code "86") (name "unconnected-(WIFI-IO10-Pad12)") (class "Default")
      (node (ref "WIFI") (pin "12") (pinfunction "IO10_12") (pintype "bidirectional"))
    )
    (net (code "87") (name "unconnected-(WIFI-MISO-Pad10)") (class "Default")
      (node (ref "WIFI") (pin "10") (pinfunction "MISO_10") (pintype "bidirectional"))
    )
    (net (code "88") (name "unconnected-(WIFI-MOSI-Pad13)") (class "Default")
      (node (ref "WIFI") (pin "13") (pinfunction "MOSI_13") (pintype "bidirectional"))
    )
    (net (code "89") (name "unconnected-(WIFI-SCLK-Pad14)") (class "Default")
      (node (ref "WIFI") (pin "14") (pinfunction "SCLK_14") (pintype "bidirectional"))
    )
    (net (code "90") (name "unconnected-(X1-Pad4)") (class "Default")
      (node (ref "X1") (pin "4") (pinfunction "4_4") (pintype "passive"))
    )
  )
)
